# Experiment_5_0_0_0.net
KiCad netlist of a schematic drawn in Altium Designer
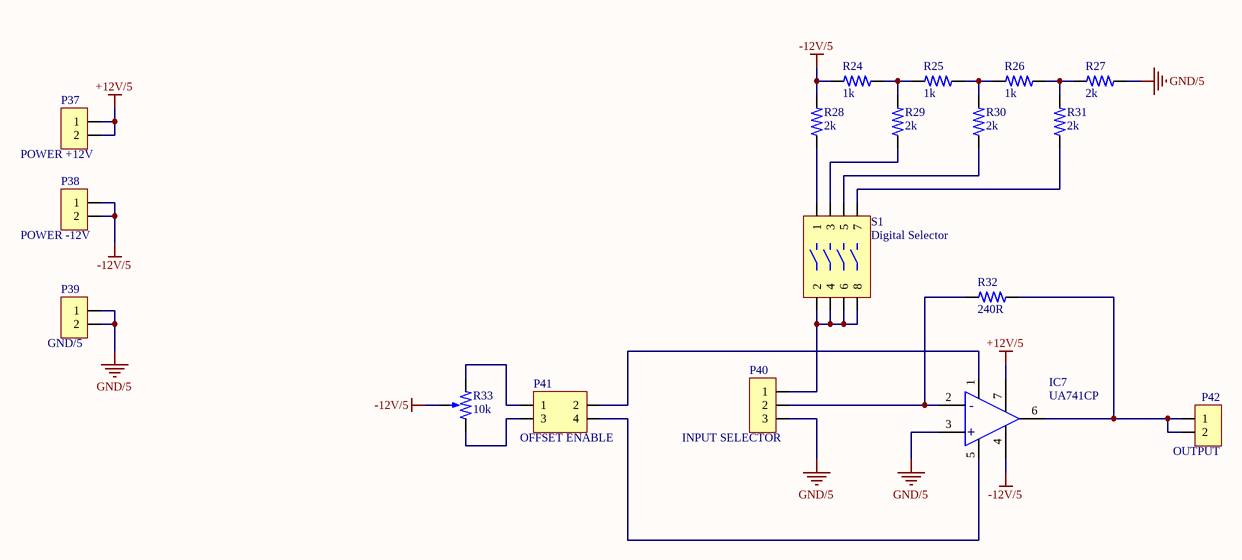
[diagram p0: Experiment 5 0.0.0.SchDoc]

(export (version "E")
  (design (tool "Eeschema 10.0.6"))
  (components
    (comp (ref "IC7")
      (value "UA741CP")
      (footprint "DIP-8")
      (description "IC OPAMP GP 1MHZ 8DIP")
      (fields (field (name "MANUFACTURER") "Texas Instruments"))
      (libsource (lib "ICs") (part "UA741CP"))
    )
    (comp (ref "P37")
      (value "POWER +12V")
      (footprint "PINHD-1X02 ONCE")
      (description "CONN HEADER 2POS .100\" STR TIN")
      (fields
        (field (name "MANUFACTURER") "Molex, LLC")
        (field (name "MANUFACTURER PART NUMBER") "0901200122")
      )
      (libsource (lib "Connectors") (part "PIN HEADER 1X02 ONCE"))
    )
    (comp (ref "P38")
      (value "POWER -12V")
      (footprint "PINHD-1X02 ONCE")
      (description "CONN HEADER 2POS .100\" STR TIN")
      (fields
        (field (name "MANUFACTURER") "Molex, LLC")
        (field (name "MANUFACTURER PART NUMBER") "0901200122")
      )
      (libsource (lib "Connectors") (part "PIN HEADER 1X02 ONCE"))
    )
    (comp (ref "P39")
      (value "GND/5")
      (footprint "PINHD-1X02 ONCE")
      (description "CONN HEADER 2POS .100\" STR TIN")
      (fields
        (field (name "MANUFACTURER") "Molex, LLC")
        (field (name "MANUFACTURER PART NUMBER") "0901200122")
      )
      (libsource (lib "Connectors") (part "PIN HEADER 1X02 ONCE"))
    )
    (comp (ref "P40")
      (value "INPUT SELECTOR")
      (footprint "PINHD-1X03")
      (description "CONN HEADER 3POS .100\" STR TIN")
      (fields
        (field (name "MANUFACTURER") "Molex, LLC")
        (field (name "MANUFACTURER PART NUMBER") "0901200123")
      )
      (libsource (lib "Connectors") (part "PIN HEADER 1X03"))
    )
    (comp (ref "P41")
      (value "OFFSET ENABLE")
      (footprint "PINHD-2X02")
      (description "CONN HEADER 4POS .100\" STR TIN")
      (fields
        (field (name "MANUFACTURER") "Molex, LLC")
        (field (name "MANUFACTURER PART NUMBER") "0901310122")
      )
      (libsource (lib "Connectors") (part "PIN HEADER 2X02"))
    )
    (comp (ref "P42")
      (value "OUTPUT")
      (footprint "PINHD-1X02 ONCE")
      (description "CONN HEADER 2POS .100\" STR TIN")
      (fields
        (field (name "MANUFACTURER") "Molex, LLC")
        (field (name "MANUFACTURER PART NUMBER") "0901200122")
      )
      (libsource (lib "") (part "PIN HEADER 1X02 ONCE_1"))
    )
    (comp (ref "R24")
      (value "1k")
      (footprint "R Axial 0.25")
      (description "RES 1K OHM 1/4W 5% AXIAL")
      (fields
        (field (name "MANUFACTURER") "Yageo")
        (field (name "MANUFACTURER PART NUMBER") "CFR-25JB-52-1K")
      )
      (libsource (lib "Resistors") (part "CFR-25JB-52-1K"))
    )
    (comp (ref "R25")
      (value "1k")
      (footprint "R Axial 0.25")
      (description "RES 1K OHM 1/4W 5% AXIAL")
      (fields
        (field (name "MANUFACTURER") "Yageo")
        (field (name "MANUFACTURER PART NUMBER") "CFR-25JB-52-1K")
      )
      (libsource (lib "Resistors") (part "CFR-25JB-52-1K"))
    )
    (comp (ref "R26")
      (value "1k")
      (footprint "R Axial 0.25")
      (description "RES 1K OHM 1/4W 5% AXIAL")
      (fields
        (field (name "MANUFACTURER") "Yageo")
        (field (name "MANUFACTURER PART NUMBER") "CFR-25JB-52-1K")
      )
      (libsource (lib "Resistors") (part "CFR-25JB-52-1K"))
    )
    (comp (ref "R27")
      (value "2k")
      (footprint "R Axial 0.25")
      (description "RES 2K OHM 1/4W 5% AXIAL")
      (fields
        (field (name "MANUFACTURER") "Yageo")
        (field (name "MANUFACTURER PART NUMBER") "CFR-25JB-52-2K")
      )
      (libsource (lib "Resistors") (part "CFR-25JB-52-2K"))
    )
    (comp (ref "R28")
      (value "2k")
      (footprint "R Axial 0.25")
      (description "RES 2K OHM 1/4W 5% AXIAL")
      (fields
        (field (name "MANUFACTURER") "Yageo")
        (field (name "MANUFACTURER PART NUMBER") "CFR-25JB-52-2K")
      )
      (libsource (lib "Resistors") (part "CFR-25JB-52-2K"))
    )
    (comp (ref "R29")
      (value "2k")
      (footprint "R Axial 0.25")
      (description "RES 2K OHM 1/4W 5% AXIAL")
      (fields
        (field (name "MANUFACTURER") "Yageo")
        (field (name "MANUFACTURER PART NUMBER") "CFR-25JB-52-2K")
      )
      (libsource (lib "Resistors") (part "CFR-25JB-52-2K"))
    )
    (comp (ref "R30")
      (value "2k")
      (footprint "R Axial 0.25")
      (description "RES 2K OHM 1/4W 5% AXIAL")
      (fields
        (field (name "MANUFACTURER") "Yageo")
        (field (name "MANUFACTURER PART NUMBER") "CFR-25JB-52-2K")
      )
      (libsource (lib "Resistors") (part "CFR-25JB-52-2K"))
    )
    (comp (ref "R31")
      (value "2k")
      (footprint "R Axial 0.25")
      (description "RES 2K OHM 1/4W 5% AXIAL")
      (fields
        (field (name "MANUFACTURER") "Yageo")
        (field (name "MANUFACTURER PART NUMBER") "CFR-25JB-52-2K")
      )
      (libsource (lib "Resistors") (part "CFR-25JB-52-2K"))
    )
    (comp (ref "R32")
      (value "240R")
      (footprint "R Axial 0.25")
      (description "RES 240 OHM 1/4W 5% AXIAL")
      (fields
        (field (name "MANUFACTURER") "Yageo")
        (field (name "MANUFACTURER PART NUMBER") "CFR-25JB-52-240R")
      )
      (libsource (lib "Resistors") (part "CFR-25JB-52-240R"))
    )
    (comp (ref "R33")
      (value "10k")
      (footprint "PV36W")
      (description "TRIMMER 10K OHM 0.5W TH")
      (fields
        (field (name "MANUFACTURER") "Bourns Inc.")
        (field (name "MANUFACTURER PART NUMBER") "PV36W103C01B00")
      )
      (libsource (lib "Resistors") (part "PV36W103C01B00"))
    )
    (comp (ref "S1")
      (value "Digital Selector")
      (footprint "DIP-206-4S")
      (description "SWITCH SLIDE DIP SPST 50MA 24V")
      (fields
        (field (name "MANUFACTURER") "CTS Electrocomponents")
        (field (name "MANUFACTURER PART NUMBER") "206-4")
      )
      (libsource (lib "Switches") (part "206-4"))
    )
  )
  (nets
    (net (code "1") (name "+12V{slash}5") (class "Default")
      (node (ref "IC7") (pin "7") (pinfunction "VCC+_7") (pintype "power_in"))
      (node (ref "P37") (pin "1") (pinfunction "1_1") (pintype "passive"))
      (node (ref "P37") (pin "2") (pinfunction "2_2") (pintype "passive"))
    )
    (net (code "2") (name "-12V{slash}5") (class "Default")
      (node (ref "IC7") (pin "4") (pinfunction "VCC-_4") (pintype "power_in"))
      (node (ref "P38") (pin "1") (pinfunction "1_1") (pintype "passive"))
      (node (ref "P38") (pin "2") (pinfunction "2_2") (pintype "passive"))
      (node (ref "R24") (pin "1") (pinfunction "1_1") (pintype "passive"))
      (node (ref "R28") (pin "2") (pinfunction "2_2") (pintype "passive"))
      (node (ref "R33") (pin "2") (pinfunction "2_2") (pintype "passive"))
    )
    (net (code "3") (name "GND{slash}5") (class "Default")
      (node (ref "IC7") (pin "3") (pinfunction "+_3") (pintype "passive"))
      (node (ref "P39") (pin "1") (pinfunction "1_1") (pintype "passive"))
      (node (ref "P39") (pin "2") (pinfunction "2_2") (pintype "passive"))
      (node (ref "P40") (pin "3") (pinfunction "3_3") (pintype "passive"))
      (node (ref "R27") (pin "2") (pinfunction "2_2") (pintype "passive"))
    )
    (net (code "4") (name "Net-(IC7--)") (class "Default")
      (node (ref "IC7") (pin "2") (pinfunction "-_2") (pintype "passive"))
      (node (ref "P40") (pin "2") (pinfunction "2_2") (pintype "passive"))
      (node (ref "R32") (pin "1") (pinfunction "1_1") (pintype "passive"))
    )
    (net (code "5") (name "Net-(IC7-OFFSET1)") (class "Default")
      (node (ref "IC7") (pin "1") (pinfunction "OFFSET1_1") (pintype "passive"))
      (node (ref "P41") (pin "2") (pinfunction "2_2") (pintype "passive"))
    )
    (net (code "6") (name "Net-(IC7-OFFSET2)") (class "Default")
      (node (ref "IC7") (pin "5") (pinfunction "OFFSET2_5") (pintype "passive"))
      (node (ref "P41") (pin "4") (pinfunction "4_4") (pintype "passive"))
    )
    (net (code "7") (name "Net-(IC7-OUTPUT)") (class "Default")
      (node (ref "IC7") (pin "6") (pinfunction "OUTPUT_6") (pintype "passive"))
      (node (ref "P42") (pin "1") (pinfunction "1_1") (pintype "passive"))
      (node (ref "P42") (pin "2") (pinfunction "2_2") (pintype "passive"))
      (node (ref "R32") (pin "2") (pinfunction "2_2") (pintype "passive"))
    )
    (net (code "8") (name "Net-(P40-Pad1)") (class "Default")
      (node (ref "P40") (pin "1") (pinfunction "1_1") (pintype "passive"))
      (node (ref "S1") (pin "2") (pinfunction "2_2") (pintype "passive"))
      (node (ref "S1") (pin "4") (pinfunction "4_4") (pintype "passive"))
      (node (ref "S1") (pin "6") (pinfunction "6_6") (pintype "passive"))
      (node (ref "S1") (pin "8") (pinfunction "8_8") (pintype "passive"))
    )
    (net (code "9") (name "Net-(P41-Pad1)") (class "Default")
      (node (ref "P41") (pin "1") (pinfunction "1_1") (pintype "passive"))
      (node (ref "R33") (pin "1") (pinfunction "1_1") (pintype "passive"))
    )
    (net (code "10") (name "Net-(P41-Pad3)") (class "Default")
      (node (ref "P41") (pin "3") (pinfunction "3_3") (pintype "passive"))
      (node (ref "R33") (pin "3") (pinfunction "3_3") (pintype "passive"))
    )
    (net (code "11") (name "Net-(R24-Pad2)") (class "Default")
      (node (ref "R24") (pin "2") (pinfunction "2_2") (pintype "passive"))
      (node (ref "R25") (pin "1") (pinfunction "1_1") (pintype "passive"))
      (node (ref "R29") (pin "2") (pinfunction "2_2") (pintype "passive"))
    )
    (net (code "12") (name "Net-(R25-Pad2)") (class "Default")
      (node (ref "R25") (pin "2") (pinfunction "2_2") (pintype "passive"))
      (node (ref "R26") (pin "1") (pinfunction "1_1") (pintype "passive"))
      (node (ref "R30") (pin "2") (pinfunction "2_2") (pintype "passive"))
    )
    (net (code "13") (name "Net-(R26-Pad2)") (class "Default")
      (node (ref "R26") (pin "2") (pinfunction "2_2") (pintype "passive"))
      (node (ref "R27") (pin "1") (pinfunction "1_1") (pintype "passive"))
      (node (ref "R31") (pin "2") (pinfunction "2_2") (pintype "passive"))
    )
    (net (code "14") (name "Net-(R28-Pad1)") (class "Default")
      (node (ref "R28") (pin "1") (pinfunction "1_1") (pintype "passive"))
      (node (ref "S1") (pin "1") (pinfunction "1_1") (pintype "passive"))
    )
    (net (code "15") (name "Net-(R29-Pad1)") (class "Default")
      (node (ref "R29") (pin "1") (pinfunction "1_1") (pintype "passive"))
      (node (ref "S1") (pin "3") (pinfunction "3_3") (pintype "passive"))
    )
    (net (code "16") (name "Net-(R30-Pad1)") (class "Default")
      (node (ref "R30") (pin "1") (pinfunction "1_1") (pintype "passive"))
      (node (ref "S1") (pin "5") (pinfunction "5_5") (pintype "passive"))
    )
    (net (code "17") (name "Net-(R31-Pad1)") (class "Default")
      (node (ref "R31") (pin "1") (pinfunction "1_1") (pintype "passive"))
      (node (ref "S1") (pin "7") (pinfunction "7_7") (pintype "passive"))
    )
  )
)
